# MicroController.net
KiCad netlist of a schematic drawn in Altium Designer
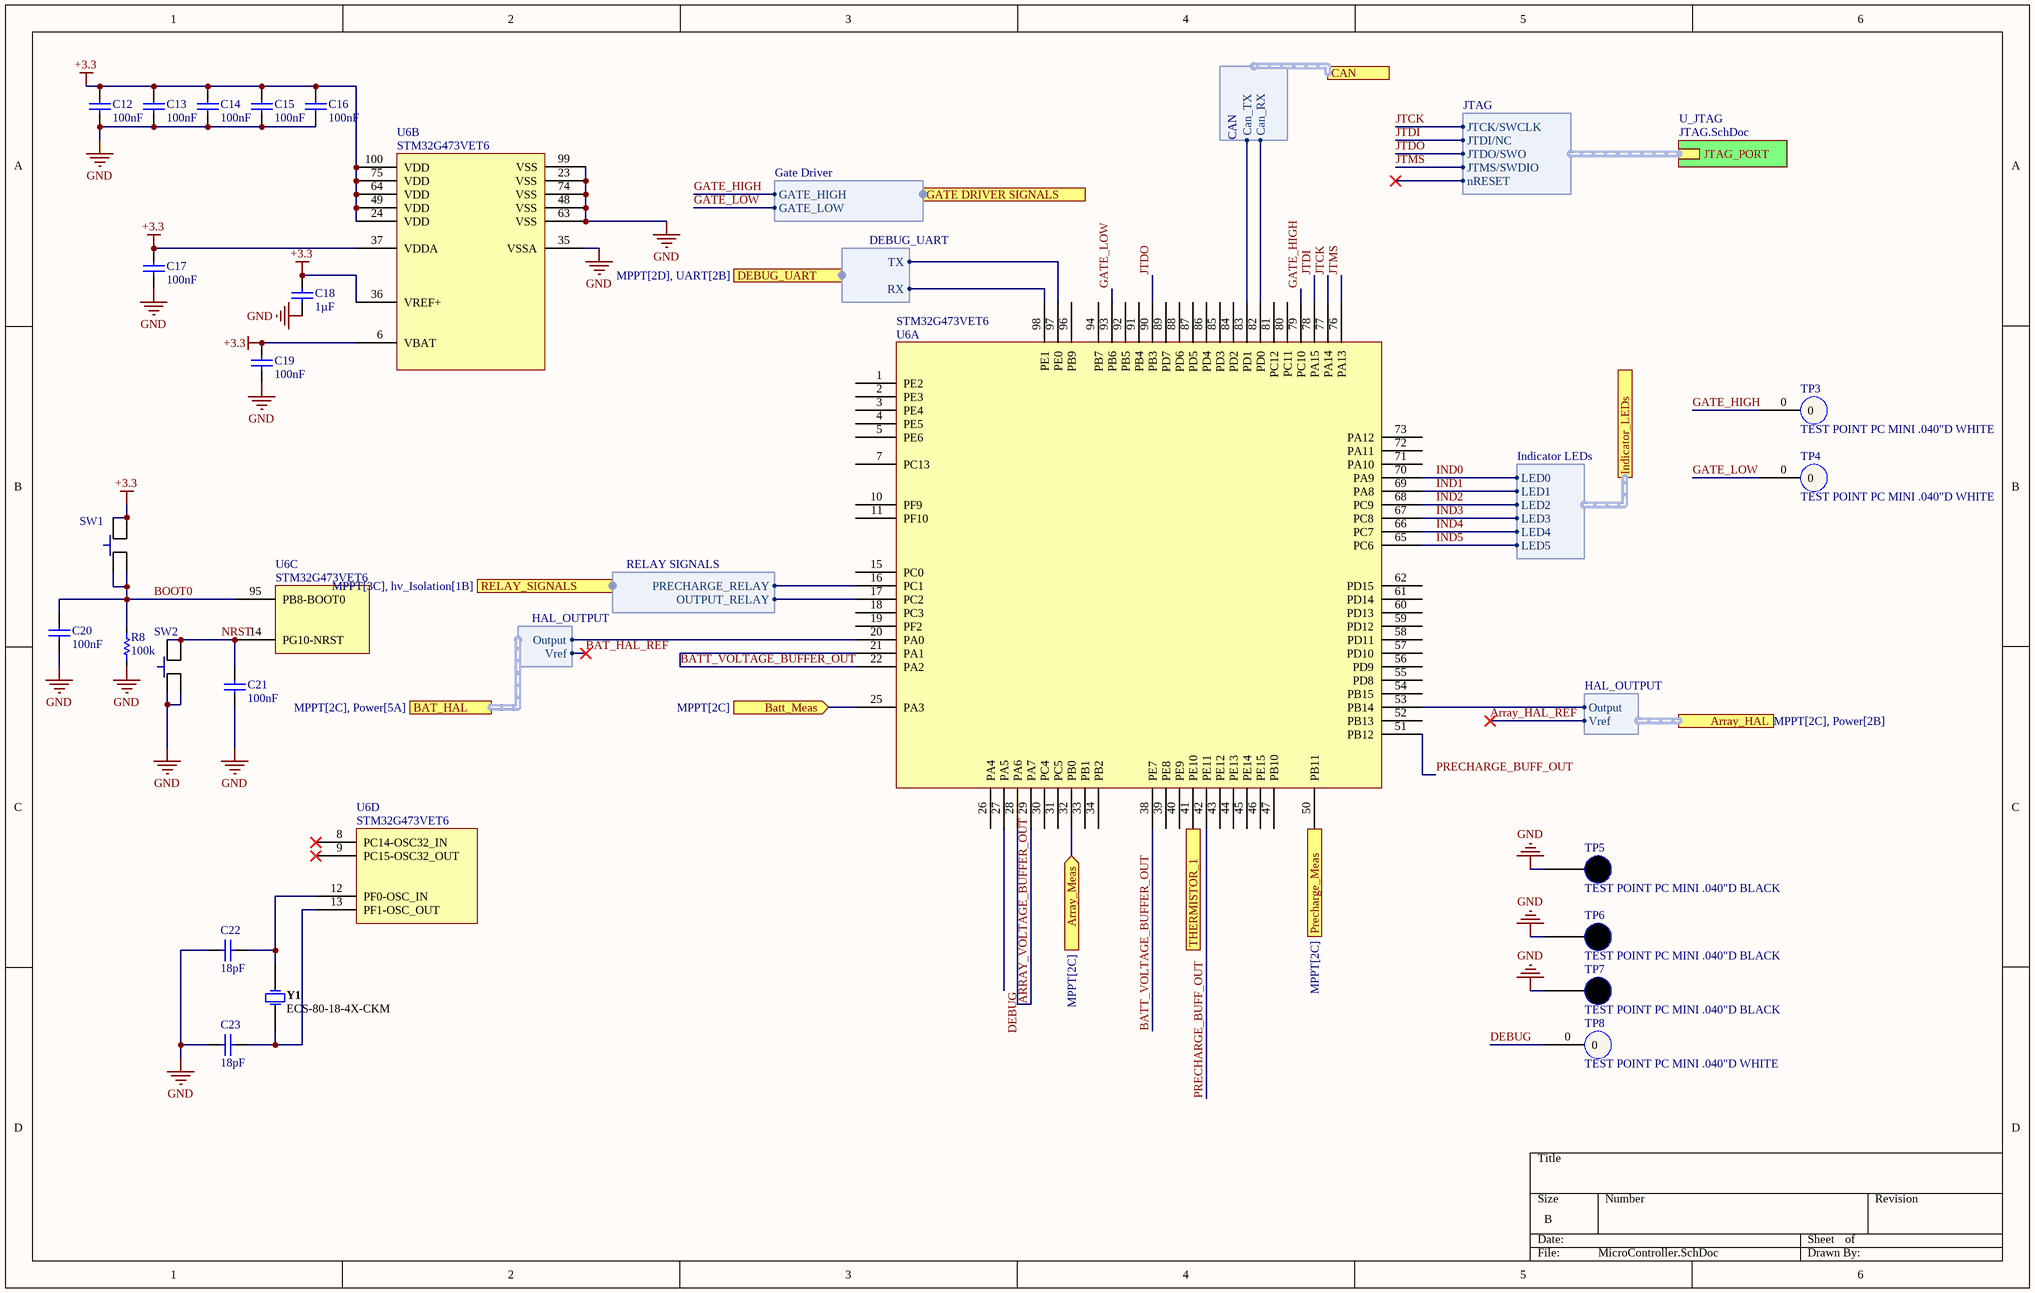
[diagram p0: MicroController.SchDoc]

(export (version "E")
  (design (tool "Eeschema 10.0.6"))
  (components
    (comp (ref "C12")
      (value "100nF")
      (footprint "CAPC1608X90X40ML10T20")
      (description "Chip Capacitor, 0.1uF, +/- 10%, 50 V, 0603 (1608 Metric)")
      (fields (field (name "TOLERANCE") "10%") (field (name "Comment") "Capacitor 0.1uF +/-10% 50 V 0603"))
      (libsource (lib "University of Minnesota - Solar Vehicle Project") (part "Cap"))
    )
    (comp (ref "C13")
      (value "100nF")
      (footprint "CAPC1608X90X40ML10T20")
      (description "Chip Capacitor, 0.1uF, +/- 10%, 50 V, 0603 (1608 Metric)")
      (fields (field (name "TOLERANCE") "10%") (field (name "Comment") "Capacitor 0.1uF +/-10% 50 V 0603"))
      (libsource (lib "University of Minnesota - Solar Vehicle Project") (part "Cap"))
    )
    (comp (ref "C14")
      (value "100nF")
      (footprint "CAPC1608X90X40ML10T20")
      (description "Chip Capacitor, 0.1uF, +/- 10%, 50 V, 0603 (1608 Metric)")
      (fields (field (name "TOLERANCE") "10%") (field (name "Comment") "Capacitor 0.1uF +/-10% 50 V 0603"))
      (libsource (lib "University of Minnesota - Solar Vehicle Project") (part "Cap"))
    )
    (comp (ref "C15")
      (value "100nF")
      (footprint "CAPC1608X90X40ML10T20")
      (description "Chip Capacitor, 0.1uF, +/- 10%, 50 V, 0603 (1608 Metric)")
      (fields (field (name "TOLERANCE") "10%") (field (name "Comment") "Capacitor 0.1uF +/-10% 50 V 0603"))
      (libsource (lib "University of Minnesota - Solar Vehicle Project") (part "Cap"))
    )
    (comp (ref "C16")
      (value "100nF")
      (footprint "CAPC1608X90X40ML10T20")
      (description "Chip Capacitor, 0.1uF, +/- 10%, 50 V, 0603 (1608 Metric)")
      (fields (field (name "TOLERANCE") "10%") (field (name "Comment") "Capacitor 0.1uF +/-10% 50 V 0603"))
      (libsource (lib "University of Minnesota - Solar Vehicle Project") (part "Cap"))
    )
    (comp (ref "C17")
      (value "100nF")
      (footprint "CAPC1608X90X40ML10T20")
      (description "Chip Capacitor, 0.1uF, +/- 10%, 50 V, 0603 (1608 Metric)")
      (fields (field (name "TOLERANCE") "10%") (field (name "Comment") "Capacitor 0.1uF +/-10% 50 V 0603"))
      (libsource (lib "University of Minnesota - Solar Vehicle Project") (part "Cap"))
    )
    (comp (ref "C18")
      (value "1µF")
      (footprint "0805_Capacitor")
      (description "CAP 0805 1uF 50V")
      (fields (field (name "TOLERANCE") "10%"))
      (libsource (lib "University of Minnesota - Solar Vehicle Project") (part "Cap"))
    )
    (comp (ref "C19")
      (value "100nF")
      (footprint "CAPC1608X90X40ML10T20")
      (description "Chip Capacitor, 0.1uF, +/- 10%, 50 V, 0603 (1608 Metric)")
      (fields (field (name "TOLERANCE") "10%") (field (name "Comment") "Capacitor 0.1uF +/-10% 50 V 0603"))
      (libsource (lib "University of Minnesota - Solar Vehicle Project") (part "Cap"))
    )
    (comp (ref "C20")
      (value "100nF")
      (footprint "CAPC1608X90X40ML10T20")
      (description "Chip Capacitor, 0.1uF, +/- 10%, 50 V, 0603 (1608 Metric)")
      (fields (field (name "TOLERANCE") "10%") (field (name "Comment") "Capacitor 0.1uF +/-10% 50 V 0603"))
      (libsource (lib "University of Minnesota - Solar Vehicle Project") (part "Cap"))
    )
    (comp (ref "C21")
      (value "100nF")
      (footprint "CAPC1608X90X40ML10T20")
      (description "Chip Capacitor, 0.1uF, +/- 10%, 50 V, 0603 (1608 Metric)")
      (fields (field (name "TOLERANCE") "10%") (field (name "Comment") "Capacitor 0.1uF +/-10% 50 V 0603"))
      (libsource (lib "University of Minnesota - Solar Vehicle Project") (part "Cap"))
    )
    (comp (ref "C22")
      (value "18pF")
      (footprint "0603_CAPACITOR")
      (description "Capacitor 18pF ceramic 0603 10% 50V")
      (fields (field (name "TOLERANCE") "10%") (field (name "Comment") "Capacitor 18pF 0603 50V 10%"))
      (libsource (lib "University of Minnesota - Solar Vehicle Project") (part "Cap"))
    )
    (comp (ref "C23")
      (value "18pF")
      (footprint "0603_CAPACITOR")
      (description "Capacitor 18pF ceramic 0603 10% 50V")
      (fields (field (name "TOLERANCE") "10%") (field (name "Comment") "Capacitor 18pF 0603 50V 10%"))
      (libsource (lib "University of Minnesota - Solar Vehicle Project") (part "Cap"))
    )
    (comp (ref "R8")
      (value "100k")
      (footprint "0603_RESISTOR")
      (description "RES 100K OHM 1/16W 1% 0603 SMD")
      (fields (field (name "POWER") "62.5mW") (field (name "TOLERANCE") "1%"))
      (libsource (lib "University of Minnesota - Solar Vehicle Project") (part "Symbol"))
    )
    (comp (ref "SW1")
      (value "SW_TACT_SWITCH_6x6")
      (footprint "TACT_SWITCH_6x6_J-LEAD")
      (description "SWITCH TACT 6MM BLACK 160GF")
      (fields (field (name "SVP CREATOR") "Spencer Berglund"))
      (libsource (lib "University of Minnesota - Solar Vehicle Project") (part "SW_TACT_SWITCH_6x6"))
    )
    (comp (ref "SW2")
      (value "SW_TACT_SWITCH_6x6")
      (footprint "TACT_SWITCH_6x6_J-LEAD")
      (description "SWITCH TACT 6MM BLACK 160GF")
      (fields (field (name "SVP CREATOR") "Spencer Berglund"))
      (libsource (lib "University of Minnesota - Solar Vehicle Project") (part "SW_TACT_SWITCH_6x6"))
    )
    (comp (ref "TP3")
      (value "TEST POINT PC MINI .040\"D WHITE")
      (footprint "TEST POINT 0.040\" WHITE")
      (libsource (lib "University of Minnesota - Solar Vehicle Project") (part "TEST POINT PC MINI .040{dblquote}D WHITE"))
    )
    (comp (ref "TP4")
      (value "TEST POINT PC MINI .040\"D WHITE")
      (footprint "TEST POINT 0.040\" WHITE")
      (libsource (lib "University of Minnesota - Solar Vehicle Project") (part "TEST POINT PC MINI .040{dblquote}D WHITE"))
    )
    (comp (ref "TP5")
      (value "TEST POINT PC MINI .040\"D BLACK")
      (footprint "TEST POINT 0.040\" BLACK")
      (libsource (lib "University of Minnesota - Solar Vehicle Project") (part "TEST POINT PC MINI .040{dblquote}D BLACK"))
    )
    (comp (ref "TP6")
      (value "TEST POINT PC MINI .040\"D BLACK")
      (footprint "TEST POINT 0.040\" BLACK")
      (libsource (lib "University of Minnesota - Solar Vehicle Project") (part "TEST POINT PC MINI .040{dblquote}D BLACK"))
    )
    (comp (ref "TP7")
      (value "TEST POINT PC MINI .040\"D BLACK")
      (footprint "TEST POINT 0.040\" BLACK")
      (libsource (lib "University of Minnesota - Solar Vehicle Project") (part "TEST POINT PC MINI .040{dblquote}D BLACK"))
    )
    (comp (ref "TP8")
      (value "TEST POINT PC MINI .040\"D WHITE")
      (footprint "TEST POINT 0.040\" WHITE")
      (libsource (lib "University of Minnesota - Solar Vehicle Project") (part "TEST POINT PC MINI .040{dblquote}D WHITE"))
    )
    (comp (ref "U6")
      (value "STM32G473VET6")
      (footprint "TSQFP50P1600X1600X160-100N")
      (description "RISC Microcontroller, 32-Bit, 170MHz")
      (libsource (lib "University of Minnesota - Solar Vehicle Project") (part "STM32G473VET6-Symbol-1"))
    )
    (comp (ref "Y1")
      (value "ECS-80-18-4X-CKM")
      (footprint "ECS-80-18-4X-CKM-Footprint-1")
      (description "Crystal 8MHz ±10ppm (Tol) ±10ppm (Stability) 18pF FUND 80Ohm 2-Pin HC-49/USX Thru-Hole Bulk")
      (libsource (lib "University of Minnesota - Solar Vehicle Project") (part "XTAL-2"))
    )
  )
  (nets
    (net (code "11") (name "+3.3") (class "Default")
      (node (ref "C12") (pin "2") (pinfunction "2_2") (pintype "passive"))
      (node (ref "C13") (pin "2") (pinfunction "2_2") (pintype "passive"))
      (node (ref "C14") (pin "2") (pinfunction "2_2") (pintype "passive"))
      (node (ref "C15") (pin "2") (pinfunction "2_2") (pintype "passive"))
      (node (ref "C16") (pin "2") (pinfunction "2_2") (pintype "passive"))
      (node (ref "C17") (pin "2") (pinfunction "2_2") (pintype "passive"))
      (node (ref "C18") (pin "1") (pinfunction "1_1") (pintype "passive"))
      (node (ref "C19") (pin "2") (pinfunction "2_2") (pintype "passive"))
      (node (ref "SW1") (pin "2") (pinfunction "2_2") (pintype "passive"))
      (node (ref "SW1") (pin "3") (pinfunction "3_3") (pintype "passive"))
      (node (ref "U6") (pin "100") (pinfunction "VDD_100") (pintype "power_in"))
      (node (ref "U6") (pin "24") (pinfunction "VDD_24") (pintype "power_in"))
      (node (ref "U6") (pin "36") (pinfunction "VREF+_36") (pintype "power_in"))
      (node (ref "U6") (pin "37") (pinfunction "VDDA_37") (pintype "power_in"))
      (node (ref "U6") (pin "49") (pinfunction "VDD_49") (pintype "power_in"))
      (node (ref "U6") (pin "6") (pinfunction "VBAT_6") (pintype "power_in"))
      (node (ref "U6") (pin "64") (pinfunction "VDD_64") (pintype "power_in"))
      (node (ref "U6") (pin "75") (pinfunction "VDD_75") (pintype "power_in"))
    )
    (net (code "12") (name "/ARRAY_VOLTAGE_BUFFER_OUT") (class "Default")
      (node (ref "U6") (pin "28") (pinfunction "PA6_28") (pintype "passive"))
      (node (ref "U6") (pin "29") (pinfunction "PA7_29") (pintype "passive"))
    )
    (net (code "14") (name "/Array_Meas") (class "Default")
      (node (ref "U6") (pin "32") (pinfunction "PB0_32") (pintype "passive"))
    )
    (net (code "15") (name "/BATT_VOLTAGE_BUFFER_OUT") (class "Default")
      (node (ref "U6") (pin "21") (pinfunction "PA1_21") (pintype "passive"))
      (node (ref "U6") (pin "22") (pinfunction "PA2_22") (pintype "passive"))
      (node (ref "U6") (pin "38") (pinfunction "PE7_38") (pintype "passive"))
    )
    (net (code "17") (name "/BOOT0") (class "Default")
      (node (ref "C20") (pin "2") (pinfunction "2_2") (pintype "passive"))
      (node (ref "R8") (pin "2") (pinfunction "2_2") (pintype "passive"))
      (node (ref "SW1") (pin "1") (pinfunction "1_1") (pintype "passive"))
      (node (ref "SW1") (pin "4") (pinfunction "4_4") (pintype "passive"))
      (node (ref "U6") (pin "95") (pinfunction "PB8-BOOT0_95") (pintype "passive"))
    )
    (net (code "18") (name "/Batt_Meas") (class "Default")
      (node (ref "U6") (pin "25") (pinfunction "PA3_25") (pintype "passive"))
    )
    (net (code "19") (name "/Can_RX") (class "Default")
      (node (ref "U6") (pin "82") (pinfunction "PD0_82") (pintype "passive"))
    )
    (net (code "20") (name "/Can_TX") (class "Default")
      (node (ref "U6") (pin "83") (pinfunction "PD1_83") (pintype "passive"))
    )
    (net (code "21") (name "/DEBUG") (class "Default")
      (node (ref "TP8") (pin "0") (pinfunction "0_0") (pintype "passive"))
      (node (ref "U6") (pin "27") (pinfunction "PA5_27") (pintype "passive"))
    )
    (net (code "22") (name "/GATE_HIGH") (class "Default")
      (node (ref "TP3") (pin "0") (pinfunction "0_0") (pintype "passive"))
      (node (ref "U6") (pin "79") (pinfunction "PC10_79") (pintype "passive"))
    )
    (net (code "23") (name "/GATE_LOW") (class "Default")
      (node (ref "TP4") (pin "0") (pinfunction "0_0") (pintype "passive"))
      (node (ref "U6") (pin "93") (pinfunction "PB6_93") (pintype "passive"))
    )
    (net (code "24") (name "/IND0") (class "Default")
      (node (ref "U6") (pin "70") (pinfunction "PA9_70") (pintype "passive"))
    )
    (net (code "25") (name "/IND1") (class "Default")
      (node (ref "U6") (pin "69") (pinfunction "PA8_69") (pintype "passive"))
    )
    (net (code "26") (name "/IND2") (class "Default")
      (node (ref "U6") (pin "68") (pinfunction "PC9_68") (pintype "passive"))
    )
    (net (code "27") (name "/IND3") (class "Default")
      (node (ref "U6") (pin "67") (pinfunction "PC8_67") (pintype "passive"))
    )
    (net (code "28") (name "/IND4") (class "Default")
      (node (ref "U6") (pin "66") (pinfunction "PC7_66") (pintype "passive"))
    )
    (net (code "29") (name "/IND5") (class "Default")
      (node (ref "U6") (pin "65") (pinfunction "PC6_65") (pintype "passive"))
    )
    (net (code "30") (name "/JTCK") (class "Default")
      (node (ref "U6") (pin "77") (pinfunction "PA14_77") (pintype "passive"))
    )
    (net (code "31") (name "/JTDI") (class "Default")
      (node (ref "U6") (pin "78") (pinfunction "PA15_78") (pintype "passive"))
    )
    (net (code "32") (name "/JTDO") (class "Default")
      (node (ref "U6") (pin "90") (pinfunction "PB3_90") (pintype "passive"))
    )
    (net (code "33") (name "/JTMS") (class "Default")
      (node (ref "U6") (pin "76") (pinfunction "PA13_76") (pintype "passive"))
    )
    (net (code "34") (name "/NRST") (class "Default")
      (node (ref "C21") (pin "2") (pinfunction "2_2") (pintype "passive"))
      (node (ref "SW2") (pin "2") (pinfunction "2_2") (pintype "passive"))
      (node (ref "SW2") (pin "3") (pinfunction "3_3") (pintype "passive"))
      (node (ref "U6") (pin "14") (pinfunction "PG10-NRST_14") (pintype "passive"))
    )
    (net (code "35") (name "/OUTPUT_RELAY") (class "Default")
      (node (ref "U6") (pin "17") (pinfunction "PC2_17") (pintype "passive"))
    )
    (net (code "36") (name "/PRECHARGE_BUFF_OUT") (class "Default")
      (node (ref "U6") (pin "42") (pinfunction "PE11_42") (pintype "passive"))
      (node (ref "U6") (pin "51") (pinfunction "PB12_51") (pintype "passive"))
    )
    (net (code "37") (name "/PRECHARGE_RELAY") (class "Default")
      (node (ref "U6") (pin "16") (pinfunction "PC1_16") (pintype "passive"))
    )
    (net (code "38") (name "/Precharge_Meas") (class "Default")
      (node (ref "U6") (pin "50") (pinfunction "PB11_50") (pintype "passive"))
    )
    (net (code "39") (name "/RX") (class "Default")
      (node (ref "U6") (pin "98") (pinfunction "PE1_98") (pintype "passive"))
    )
    (net (code "40") (name "/THERMISTOR_1") (class "Default")
      (node (ref "U6") (pin "41") (pinfunction "PE10_41") (pintype "passive"))
    )
    (net (code "41") (name "/TX") (class "Default")
      (node (ref "U6") (pin "97") (pinfunction "PE0_97") (pintype "passive"))
    )
    (net (code "50") (name "GND") (class "Default")
      (node (ref "C12") (pin "1") (pinfunction "1_1") (pintype "passive"))
      (node (ref "C13") (pin "1") (pinfunction "1_1") (pintype "passive"))
      (node (ref "C14") (pin "1") (pinfunction "1_1") (pintype "passive"))
      (node (ref "C15") (pin "1") (pinfunction "1_1") (pintype "passive"))
      (node (ref "C16") (pin "1") (pinfunction "1_1") (pintype "passive"))
      (node (ref "C17") (pin "1") (pinfunction "1_1") (pintype "passive"))
      (node (ref "C18") (pin "2") (pinfunction "2_2") (pintype "passive"))
      (node (ref "C19") (pin "1") (pinfunction "1_1") (pintype "passive"))
      (node (ref "C20") (pin "1") (pinfunction "1_1") (pintype "passive"))
      (node (ref "C21") (pin "1") (pinfunction "1_1") (pintype "passive"))
      (node (ref "C22") (pin "1") (pinfunction "1_1") (pintype "passive"))
      (node (ref "C23") (pin "1") (pinfunction "1_1") (pintype "passive"))
      (node (ref "R8") (pin "1") (pinfunction "1_1") (pintype "passive"))
      (node (ref "SW2") (pin "1") (pinfunction "1_1") (pintype "passive"))
      (node (ref "SW2") (pin "4") (pinfunction "4_4") (pintype "passive"))
      (node (ref "TP5") (pin "0") (pinfunction "0_0") (pintype "passive"))
      (node (ref "TP6") (pin "0") (pinfunction "0_0") (pintype "passive"))
      (node (ref "TP7") (pin "0") (pinfunction "0_0") (pintype "passive"))
      (node (ref "U6") (pin "23") (pinfunction "VSS_23") (pintype "power_in"))
      (node (ref "U6") (pin "35") (pinfunction "VSSA_35") (pintype "power_in"))
      (node (ref "U6") (pin "48") (pinfunction "VSS_48") (pintype "power_in"))
      (node (ref "U6") (pin "63") (pinfunction "VSS_63") (pintype "power_in"))
      (node (ref "U6") (pin "74") (pinfunction "VSS_74") (pintype "power_in"))
      (node (ref "U6") (pin "99") (pinfunction "VSS_99") (pintype "power_in"))
    )
    (net (code "51") (name "Net-(U6D-PF0-OSC_IN)") (class "Default")
      (node (ref "C22") (pin "2") (pinfunction "2_2") (pintype "passive"))
      (node (ref "U6") (pin "12") (pinfunction "PF0-OSC_IN_12") (pintype "passive"))
      (node (ref "Y1") (pin "2") (pinfunction "2_2") (pintype "passive"))
    )
    (net (code "52") (name "Net-(U6D-PF1-OSC_OUT)") (class "Default")
      (node (ref "C23") (pin "2") (pinfunction "2_2") (pintype "passive"))
      (node (ref "U6") (pin "13") (pinfunction "PF1-OSC_OUT_13") (pintype "passive"))
      (node (ref "Y1") (pin "1") (pinfunction "1_1") (pintype "passive"))
    )
    (net (code "53") (name "unconnected-(U6A-PA0-Pad20)") (class "Default")
      (node (ref "U6") (pin "20") (pinfunction "PA0_20") (pintype "passive"))
    )
    (net (code "54") (name "unconnected-(U6A-PA4-Pad26)") (class "Default")
      (node (ref "U6") (pin "26") (pinfunction "PA4_26") (pintype "passive"))
    )
    (net (code "55") (name "unconnected-(U6A-PA10-Pad71)") (class "Default")
      (node (ref "U6") (pin "71") (pinfunction "PA10_71") (pintype "passive"))
    )
    (net (code "56") (name "unconnected-(U6A-PA11-Pad72)") (class "Default")
      (node (ref "U6") (pin "72") (pinfunction "PA11_72") (pintype "passive"))
    )
    (net (code "57") (name "unconnected-(U6A-PA12-Pad73)") (class "Default")
      (node (ref "U6") (pin "73") (pinfunction "PA12_73") (pintype "passive"))
    )
    (net (code "58") (name "unconnected-(U6A-PB1-Pad33)") (class "Default")
      (node (ref "U6") (pin "33") (pinfunction "PB1_33") (pintype "passive"))
    )
    (net (code "59") (name "unconnected-(U6A-PB2-Pad34)") (class "Default")
      (node (ref "U6") (pin "34") (pinfunction "PB2_34") (pintype "passive"))
    )
    (net (code "60") (name "unconnected-(U6A-PB4-Pad91)") (class "Default")
      (node (ref "U6") (pin "91") (pinfunction "PB4_91") (pintype "passive"))
    )
    (net (code "61") (name "unconnected-(U6A-PB5-Pad92)") (class "Default")
      (node (ref "U6") (pin "92") (pinfunction "PB5_92") (pintype "passive"))
    )
    (net (code "62") (name "unconnected-(U6A-PB7-Pad94)") (class "Default")
      (node (ref "U6") (pin "94") (pinfunction "PB7_94") (pintype "passive"))
    )
    (net (code "63") (name "unconnected-(U6A-PB9-Pad96)") (class "Default")
      (node (ref "U6") (pin "96") (pinfunction "PB9_96") (pintype "passive"))
    )
    (net (code "64") (name "unconnected-(U6A-PB10-Pad47)") (class "Default")
      (node (ref "U6") (pin "47") (pinfunction "PB10_47") (pintype "passive"))
    )
    (net (code "65") (name "unconnected-(U6A-PB13-Pad52)") (class "Default")
      (node (ref "U6") (pin "52") (pinfunction "PB13_52") (pintype "passive"))
    )
    (net (code "66") (name "unconnected-(U6A-PB14-Pad53)") (class "Default")
      (node (ref "U6") (pin "53") (pinfunction "PB14_53") (pintype "passive"))
    )
    (net (code "67") (name "unconnected-(U6A-PB15-Pad54)") (class "Default")
      (node (ref "U6") (pin "54") (pinfunction "PB15_54") (pintype "passive"))
    )
    (net (code "68") (name "unconnected-(U6A-PC0-Pad15)") (class "Default")
      (node (ref "U6") (pin "15") (pinfunction "PC0_15") (pintype "passive"))
    )
    (net (code "69") (name "unconnected-(U6A-PC3-Pad18)") (class "Default")
      (node (ref "U6") (pin "18") (pinfunction "PC3_18") (pintype "passive"))
    )
    (net (code "70") (name "unconnected-(U6A-PC4-Pad30)") (class "Default")
      (node (ref "U6") (pin "30") (pinfunction "PC4_30") (pintype "passive"))
    )
    (net (code "71") (name "unconnected-(U6A-PC5-Pad31)") (class "Default")
      (node (ref "U6") (pin "31") (pinfunction "PC5_31") (pintype "passive"))
    )
    (net (code "72") (name "unconnected-(U6A-PC11-Pad80)") (class "Default")
      (node (ref "U6") (pin "80") (pinfunction "PC11_80") (pintype "passive"))
    )
    (net (code "73") (name "unconnected-(U6A-PC12-Pad81)") (class "Default")
      (node (ref "U6") (pin "81") (pinfunction "PC12_81") (pintype "passive"))
    )
    (net (code "74") (name "unconnected-(U6A-PC13-Pad7)") (class "Default")
      (node (ref "U6") (pin "7") (pinfunction "PC13_7") (pintype "passive"))
    )
    (net (code "75") (name "unconnected-(U6A-PD2-Pad84)") (class "Default")
      (node (ref "U6") (pin "84") (pinfunction "PD2_84") (pintype "passive"))
    )
    (net (code "76") (name "unconnected-(U6A-PD3-Pad85)") (class "Default")
      (node (ref "U6") (pin "85") (pinfunction "PD3_85") (pintype "passive"))
    )
    (net (code "77") (name "unconnected-(U6A-PD4-Pad86)") (class "Default")
      (node (ref "U6") (pin "86") (pinfunction "PD4_86") (pintype "passive"))
    )
    (net (code "78") (name "unconnected-(U6A-PD5-Pad87)") (class "Default")
      (node (ref "U6") (pin "87") (pinfunction "PD5_87") (pintype "passive"))
    )
    (net (code "79") (name "unconnected-(U6A-PD6-Pad88)") (class "Default")
      (node (ref "U6") (pin "88") (pinfunction "PD6_88") (pintype "passive"))
    )
    (net (code "80") (name "unconnected-(U6A-PD7-Pad89)") (class "Default")
      (node (ref "U6") (pin "89") (pinfunction "PD7_89") (pintype "passive"))
    )
    (net (code "81") (name "unconnected-(U6A-PD8-Pad55)") (class "Default")
      (node (ref "U6") (pin "55") (pinfunction "PD8_55") (pintype "passive"))
    )
    (net (code "82") (name "unconnected-(U6A-PD9-Pad56)") (class "Default")
      (node (ref "U6") (pin "56") (pinfunction "PD9_56") (pintype "passive"))
    )
    (net (code "83") (name "unconnected-(U6A-PD10-Pad57)") (class "Default")
      (node (ref "U6") (pin "57") (pinfunction "PD10_57") (pintype "passive"))
    )
    (net (code "84") (name "unconnected-(U6A-PD11-Pad58)") (class "Default")
      (node (ref "U6") (pin "58") (pinfunction "PD11_58") (pintype "passive"))
    )
    (net (code "85") (name "unconnected-(U6A-PD12-Pad59)") (class "Default")
      (node (ref "U6") (pin "59") (pinfunction "PD12_59") (pintype "passive"))
    )
    (net (code "86") (name "unconnected-(U6A-PD13-Pad60)") (class "Default")
      (node (ref "U6") (pin "60") (pinfunction "PD13_60") (pintype "passive"))
    )
    (net (code "87") (name "unconnected-(U6A-PD14-Pad61)") (class "Default")
      (node (ref "U6") (pin "61") (pinfunction "PD14_61") (pintype "passive"))
    )
    (net (code "88") (name "unconnected-(U6A-PD15-Pad62)") (class "Default")
      (node (ref "U6") (pin "62") (pinfunction "PD15_62") (pintype "passive"))
    )
    (net (code "89") (name "unconnected-(U6A-PE2-Pad1)") (class "Default")
      (node (ref "U6") (pin "1") (pinfunction "PE2_1") (pintype "passive"))
    )
    (net (code "90") (name "unconnected-(U6A-PE3-Pad2)") (class "Default")
      (node (ref "U6") (pin "2") (pinfunction "PE3_2") (pintype "passive"))
    )
    (net (code "91") (name "unconnected-(U6A-PE4-Pad3)") (class "Default")
      (node (ref "U6") (pin "3") (pinfunction "PE4_3") (pintype "passive"))
    )
    (net (code "92") (name "unconnected-(U6A-PE5-Pad4)") (class "Default")
      (node (ref "U6") (pin "4") (pinfunction "PE5_4") (pintype "passive"))
    )
    (net (code "93") (name "unconnected-(U6A-PE6-Pad5)") (class "Default")
      (node (ref "U6") (pin "5") (pinfunction "PE6_5") (pintype "passive"))
    )
    (net (code "94") (name "unconnected-(U6A-PE8-Pad39)") (class "Default")
      (node (ref "U6") (pin "39") (pinfunction "PE8_39") (pintype "passive"))
    )
    (net (code "95") (name "unconnected-(U6A-PE9-Pad40)") (class "Default")
      (node (ref "U6") (pin "40") (pinfunction "PE9_40") (pintype "passive"))
    )
    (net (code "96") (name "unconnected-(U6A-PE12-Pad43)") (class "Default")
      (node (ref "U6") (pin "43") (pinfunction "PE12_43") (pintype "passive"))
    )
    (net (code "97") (name "unconnected-(U6A-PE13-Pad44)") (class "Default")
      (node (ref "U6") (pin "44") (pinfunction "PE13_44") (pintype "passive"))
    )
    (net (code "98") (name "unconnected-(U6A-PE14-Pad45)") (class "Default")
      (node (ref "U6") (pin "45") (pinfunction "PE14_45") (pintype "passive"))
    )
    (net (code "99") (name "unconnected-(U6A-PE15-Pad46)") (class "Default")
      (node (ref "U6") (pin "46") (pinfunction "PE15_46") (pintype "passive"))
    )
    (net (code "100") (name "unconnected-(U6A-PF2-Pad19)") (class "Default")
      (node (ref "U6") (pin "19") (pinfunction "PF2_19") (pintype "passive"))
    )
    (net (code "101") (name "unconnected-(U6A-PF9-Pad10)") (class "Default")
      (node (ref "U6") (pin "10") (pinfunction "PF9_10") (pintype "passive"))
    )
    (net (code "102") (name "unconnected-(U6A-PF10-Pad11)") (class "Default")
      (node (ref "U6") (pin "11") (pinfunction "PF10_11") (pintype "passive"))
    )
    (net (code "103") (name "unconnected-(U6D-PC14-OSC32_IN-Pad8)") (class "Default")
      (node (ref "U6") (pin "8") (pinfunction "PC14-OSC32_IN_8") (pintype "passive+no_connect"))
    )
    (net (code "104") (name "unconnected-(U6D-PC15-OSC32_OUT-Pad9)") (class "Default")
      (node (ref "U6") (pin "9") (pinfunction "PC15-OSC32_OUT_9") (pintype "passive+no_connect"))
    )
  )
)
